# filter.net
KiCad netlist of a schematic drawn in Altium Designer
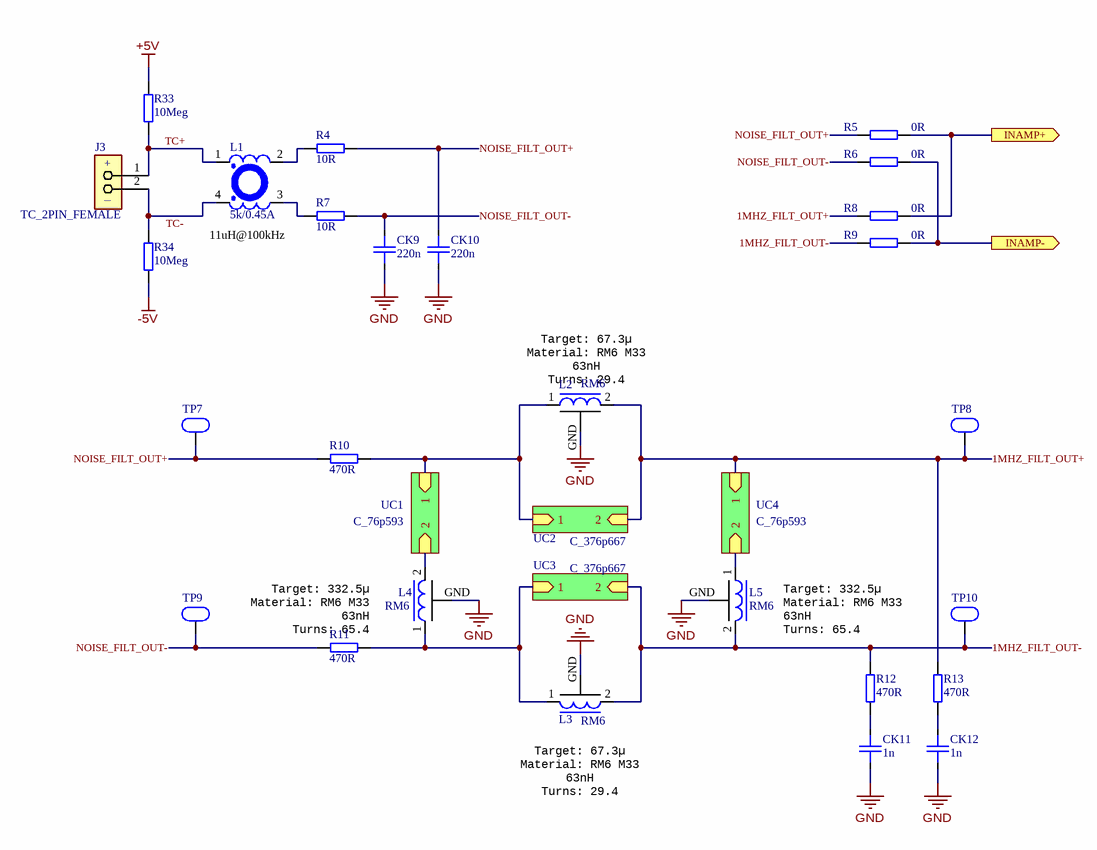
[diagram p0: filter.SchDoc]

(export (version "E")
  (design (tool "Eeschema 10.0.6"))
  (components
    (comp (ref "CK9")
      (value "220n")
      (footprint "CAPC1608X09N(SMC0603)")
      (description "C; 220n; 16V; 10%; X7R; ??;")
      (fields
        (field (name "MANUFACTURER") "TDK Corporation: C1608X7R1C224K080AC;;AVX Corporation: 0603YC224KAT2A;;Samsung: CL10B224KO8NNNC")
      )
      (libsource (lib "altium_sql") (part "CK"))
    )
    (comp (ref "CK10")
      (value "220n")
      (footprint "CAPC1608X09N(SMC0603)")
      (description "C; 220n; 16V; 10%; X7R; ??;")
      (fields
        (field (name "MANUFACTURER") "TDK Corporation: C1608X7R1C224K080AC;;AVX Corporation: 0603YC224KAT2A;;Samsung: CL10B224KO8NNNC")
      )
      (libsource (lib "altium_sql") (part "CK"))
    )
    (comp (ref "CK11")
      (value "1n")
      (footprint "CAPC2012X14N(SMC0805)")
      (description "C; 1n; 50V; 5%; NP0/C0G; ??;")
      (fields (field (name "MANUFACTURER") "YAGEO: CC0805JRNPO9BN102;;AVX: 0805 5A 102 JAT2A"))
      (libsource (lib "altium_sql") (part "CK"))
    )
    (comp (ref "CK12")
      (value "1n")
      (footprint "CAPC2012X14N(SMC0805)")
      (description "C; 1n; 50V; 5%; NP0/C0G; ??;")
      (fields (field (name "MANUFACTURER") "YAGEO: CC0805JRNPO9BN102;;AVX: 0805 5A 102 JAT2A"))
      (libsource (lib "altium_sql") (part "CK"))
    )
    (comp (ref "J3")
      (value "TC_2PIN_FEMALE")
      (footprint "TC_PCC-SMD")
      (description "Universal SMD thermocouple connector, 2 pin, Female")
      (libsource (lib "custom-footprints") (part "TC_2PIN_FEMALE"))
    )
    (comp (ref "L1")
      (value "5k/0.45A")
      (footprint "WE_744235110")
      (description "Flt; Common Mode Chokes; 0.8Ohm; 0.45A; 60V; 1x;")
      (fields (field (name "MANUFACTURER") "Würth: 744235110"))
      (libsource (lib "altium_sql") (part "L_COMP_43"))
    )
    (comp (ref "L2")
      (value "RM6")
      (footprint "RM6")
      (description "Inductor, RM6 Core")
      (libsource (lib "custom-footprints") (part "RM6"))
    )
    (comp (ref "L3")
      (value "RM6")
      (footprint "RM6")
      (description "Inductor, RM6 Core")
      (libsource (lib "") (part "RM6_1"))
    )
    (comp (ref "L4")
      (value "RM6")
      (footprint "RM6")
      (description "Inductor, RM6 Core")
      (libsource (lib "custom-footprints") (part "RM6"))
    )
    (comp (ref "L5")
      (value "RM6")
      (footprint "RM6")
      (description "Inductor, RM6 Core")
      (libsource (lib "custom-footprints") (part "RM6"))
    )
    (comp (ref "R4")
      (value "10R")
      (footprint "RESC2012X06N(SMR0805)")
      (description "R; 10R; 0.125W; 1%; 150V; Thick Film; ±200ppm/K; 1x;")
      (libsource (lib "altium_sql") (part "R"))
    )
    (comp (ref "R5")
      (value "0R")
      (footprint "RESC2012X06N(SMR0805)")
      (description "R; 0R; 0.125W; 1%; 150V; Thick Film; ±200ppm/K; 1x;")
      (fields
        (field (name "MANUFACTURER") "YAGEO: RC0805JR-100RL;;YAGEO: RC0805JR-130RL;;YAGEO: RC0805JR-070RL")
      )
      (libsource (lib "altium_sql") (part "R"))
    )
    (comp (ref "R6")
      (value "0R")
      (footprint "RESC2012X06N(SMR0805)")
      (description "R; 0R; 0.125W; 1%; 150V; Thick Film; ±200ppm/K; 1x;")
      (fields
        (field (name "MANUFACTURER") "YAGEO: RC0805JR-100RL;;YAGEO: RC0805JR-130RL;;YAGEO: RC0805JR-070RL")
      )
      (libsource (lib "altium_sql") (part "R"))
    )
    (comp (ref "R7")
      (value "10R")
      (footprint "RESC2012X06N(SMR0805)")
      (description "R; 10R; 0.125W; 1%; 150V; Thick Film; ±200ppm/K; 1x;")
      (libsource (lib "altium_sql") (part "R"))
    )
    (comp (ref "R8")
      (value "0R")
      (footprint "RESC2012X06N(SMR0805)")
      (description "R; 0R; 0.125W; 1%; 150V; Thick Film; ±200ppm/K; 1x;")
      (fields
        (field (name "MANUFACTURER") "YAGEO: RC0805JR-100RL;;YAGEO: RC0805JR-130RL;;YAGEO: RC0805JR-070RL")
      )
      (libsource (lib "altium_sql") (part "R"))
    )
    (comp (ref "R9")
      (value "0R")
      (footprint "RESC2012X06N(SMR0805)")
      (description "R; 0R; 0.125W; 1%; 150V; Thick Film; ±200ppm/K; 1x;")
      (fields
        (field (name "MANUFACTURER") "YAGEO: RC0805JR-100RL;;YAGEO: RC0805JR-130RL;;YAGEO: RC0805JR-070RL")
      )
      (libsource (lib "altium_sql") (part "R"))
    )
    (comp (ref "R10")
      (value "470R")
      (footprint "RESC1608X06N(SMR0603)")
      (description "R; 470R; 0.1W; 1%; 75V; Thick Film; ±100ppm/K; 1x;")
      (fields (field (name "MANUFACTURER") "Yageo: RC0603FR-07470RL;;Panasonic: ERJ3EKF4700V"))
      (libsource (lib "altium_sql") (part "R"))
    )
    (comp (ref "R11")
      (value "470R")
      (footprint "RESC1608X06N(SMR0603)")
      (description "R; 470R; 0.1W; 1%; 75V; Thick Film; ±100ppm/K; 1x;")
      (fields (field (name "MANUFACTURER") "Yageo: RC0603FR-07470RL;;Panasonic: ERJ3EKF4700V"))
      (libsource (lib "altium_sql") (part "R"))
    )
    (comp (ref "R12")
      (value "470R")
      (footprint "RESC1608X06N(SMR0603)")
      (description "R; 470R; 0.1W; 1%; 75V; Thick Film; ±100ppm/K; 1x;")
      (fields (field (name "MANUFACTURER") "Yageo: RC0603FR-07470RL;;Panasonic: ERJ3EKF4700V"))
      (libsource (lib "altium_sql") (part "R"))
    )
    (comp (ref "R13")
      (value "470R")
      (footprint "RESC1608X06N(SMR0603)")
      (description "R; 470R; 0.1W; 1%; 75V; Thick Film; ±100ppm/K; 1x;")
      (fields (field (name "MANUFACTURER") "Yageo: RC0603FR-07470RL;;Panasonic: ERJ3EKF4700V"))
      (libsource (lib "altium_sql") (part "R"))
    )
    (comp (ref "R33")
      (value "10Meg")
      (footprint "RESC2012X06N(SMR0805)")
      (description "R; 10Meg; 0.125W; 5%; 150V; Thick Film; ±100ppm/K; 1x;")
      (fields
        (field (name "MANUFACTURER") "YAGEO: RC0805JR-0710ML;;BC Components: MCU0805-50 1% P5 10M;;PANASONIC: ERJ 6GE Y J 106 V")
      )
      (libsource (lib "altium_sql") (part "R"))
    )
    (comp (ref "R34")
      (value "10Meg")
      (footprint "RESC2012X06N(SMR0805)")
      (description "R; 10Meg; 0.125W; 5%; 150V; Thick Film; ±100ppm/K; 1x;")
      (fields
        (field (name "MANUFACTURER") "YAGEO: RC0805JR-0710ML;;BC Components: MCU0805-50 1% P5 10M;;PANASONIC: ERJ 6GE Y J 106 V")
      )
      (libsource (lib "altium_sql") (part "R"))
    )
    (comp (ref "TP7")
      (value "Test Point")
      (footprint "SMD_Testpoint_Onelayer")
      (description "Con; Test Point; 1x; PCB; ??; ??V; ??A; ??; Tin; Contact;")
      (fields (field (name "MANUFACTURER") "Harwin: S1751-46R") (field (name "CONNECTOR_PART") "Contact"))
      (libsource (lib "altium_sql") (part "EJ+TESTPOINTXX0"))
    )
    (comp (ref "TP8")
      (value "Test Point")
      (footprint "SMD_Testpoint_Onelayer")
      (description "Con; Test Point; 1x; PCB; ??; ??V; ??A; ??; Tin; Contact;")
      (fields (field (name "MANUFACTURER") "Harwin: S1751-46R") (field (name "CONNECTOR_PART") "Contact"))
      (libsource (lib "altium_sql") (part "EJ+TESTPOINTXX0"))
    )
    (comp (ref "TP9")
      (value "Test Point")
      (footprint "SMD_Testpoint_Onelayer")
      (description "Con; Test Point; 1x; PCB; ??; ??V; ??A; ??; Tin; Contact;")
      (fields (field (name "MANUFACTURER") "Harwin: S1751-46R") (field (name "CONNECTOR_PART") "Contact"))
      (libsource (lib "altium_sql") (part "EJ+TESTPOINTXX0"))
    )
    (comp (ref "TP10")
      (value "Test Point")
      (footprint "SMD_Testpoint_Onelayer")
      (description "Con; Test Point; 1x; PCB; ??; ??V; ??A; ??; Tin; Contact;")
      (fields (field (name "MANUFACTURER") "Harwin: S1751-46R") (field (name "CONNECTOR_PART") "Contact"))
      (libsource (lib "altium_sql") (part "EJ+TESTPOINTXX0"))
    )
  )
  (nets
    (net (code "1") (name "+5V") (class "Default")
      (node (ref "R33") (pin "2") (pinfunction "2_2") (pintype "passive"))
    )
    (net (code "2") (name "-5V") (class "Default")
      (node (ref "R34") (pin "1") (pinfunction "1_1") (pintype "passive"))
    )
    (net (code "3") (name "/1") (class "Default")
      (node (ref "L2") (pin "1") (pinfunction "1_1") (pintype "passive"))
      (node (ref "R10") (pin "2") (pinfunction "2_2") (pintype "passive"))
    )
    (net (code "4") (name "/1MHZ_FILT_OUT+") (class "Default")
      (node (ref "L2") (pin "2") (pinfunction "2_2") (pintype "passive"))
      (node (ref "R13") (pin "2") (pinfunction "2_2") (pintype "passive"))
      (node (ref "R8") (pin "1") (pinfunction "1_1") (pintype "passive"))
      (node (ref "TP8") (pin "1") (pintype "passive"))
    )
    (net (code "5") (name "/1MHZ_FILT_OUT-") (class "Default")
      (node (ref "L3") (pin "2") (pinfunction "2_2") (pintype "passive"))
      (node (ref "L5") (pin "2") (pinfunction "2_2") (pintype "passive"))
      (node (ref "R12") (pin "2") (pinfunction "2_2") (pintype "passive"))
      (node (ref "R9") (pin "1") (pinfunction "1_1") (pintype "passive"))
      (node (ref "TP10") (pin "1") (pintype "passive"))
    )
    (net (code "6") (name "/1_1") (class "Default")
      (node (ref "L3") (pin "1") (pinfunction "1_1") (pintype "passive"))
      (node (ref "L4") (pin "1") (pinfunction "1_1") (pintype "passive"))
      (node (ref "R11") (pin "2") (pinfunction "2_2") (pintype "passive"))
    )
    (net (code "7") (name "/2") (class "Default")
      (node (ref "L5") (pin "1") (pinfunction "1_1") (pintype "passive"))
    )
    (net (code "8") (name "/2_1") (class "Default")
      (node (ref "L4") (pin "2") (pinfunction "2_2") (pintype "passive"))
    )
    (net (code "9") (name "/INAMP+") (class "Default")
      (node (ref "R5") (pin "2") (pinfunction "2_2") (pintype "passive"))
      (node (ref "R8") (pin "2") (pinfunction "2_2") (pintype "passive"))
    )
    (net (code "10") (name "/INAMP-") (class "Default")
      (node (ref "R6") (pin "2") (pinfunction "2_2") (pintype "passive"))
      (node (ref "R9") (pin "2") (pinfunction "2_2") (pintype "passive"))
    )
    (net (code "11") (name "/NOISE_FILT_OUT+") (class "Default")
      (node (ref "CK10") (pin "1") (pinfunction "1_1") (pintype "passive"))
      (node (ref "R10") (pin "1") (pinfunction "1_1") (pintype "passive"))
      (node (ref "R4") (pin "1") (pinfunction "1_1") (pintype "passive"))
      (node (ref "R5") (pin "1") (pinfunction "1_1") (pintype "passive"))
      (node (ref "TP7") (pin "1") (pintype "passive"))
    )
    (net (code "12") (name "/NOISE_FILT_OUT-") (class "Default")
      (node (ref "CK9") (pin "1") (pinfunction "1_1") (pintype "passive"))
      (node (ref "R11") (pin "1") (pinfunction "1_1") (pintype "passive"))
      (node (ref "R6") (pin "1") (pinfunction "1_1") (pintype "passive"))
      (node (ref "R7") (pin "2") (pinfunction "2_2") (pintype "passive"))
      (node (ref "TP9") (pin "1") (pintype "passive"))
    )
    (net (code "13") (name "/TC+") (class "Default")
      (node (ref "J3") (pin "1") (pinfunction "1_1") (pintype "passive"))
      (node (ref "L1") (pin "1") (pinfunction "L1A_1") (pintype "passive"))
      (node (ref "R33") (pin "1") (pinfunction "1_1") (pintype "passive"))
    )
    (net (code "14") (name "/TC-") (class "Default")
      (node (ref "J3") (pin "2") (pinfunction "2_2") (pintype "passive"))
      (node (ref "L1") (pin "4") (pinfunction "L2B_4") (pintype "passive"))
      (node (ref "R34") (pin "2") (pinfunction "2_2") (pintype "passive"))
    )
    (net (code "15") (name "GND") (class "Default")
      (node (ref "CK10") (pin "2") (pinfunction "2_2") (pintype "passive"))
      (node (ref "CK11") (pin "1") (pinfunction "1_1") (pintype "passive"))
      (node (ref "CK12") (pin "1") (pinfunction "1_1") (pintype "passive"))
      (node (ref "CK9") (pin "2") (pinfunction "2_2") (pintype "passive"))
      (node (ref "L2") (pin "GND") (pinfunction "GND_GND") (pintype "power_in"))
      (node (ref "L3") (pin "GND") (pinfunction "GND_GND") (pintype "power_in"))
      (node (ref "L4") (pin "GND") (pinfunction "GND_GND") (pintype "power_in"))
      (node (ref "L5") (pin "GND") (pinfunction "GND_GND") (pintype "power_in"))
    )
    (net (code "16") (name "Net-(CK11-Pad2)") (class "Default")
      (node (ref "CK11") (pin "2") (pinfunction "2_2") (pintype "passive"))
      (node (ref "R12") (pin "1") (pinfunction "1_1") (pintype "passive"))
    )
    (net (code "17") (name "Net-(CK12-Pad2)") (class "Default")
      (node (ref "CK12") (pin "2") (pinfunction "2_2") (pintype "passive"))
      (node (ref "R13") (pin "1") (pinfunction "1_1") (pintype "passive"))
    )
    (net (code "18") (name "Net-(L1-L1B)") (class "Default")
      (node (ref "L1") (pin "2") (pinfunction "L1B_2") (pintype "passive"))
      (node (ref "R4") (pin "2") (pinfunction "2_2") (pintype "passive"))
    )
    (net (code "19") (name "Net-(L1-L2A)") (class "Default")
      (node (ref "L1") (pin "3") (pinfunction "L2A_3") (pintype "passive"))
      (node (ref "R7") (pin "1") (pinfunction "1_1") (pintype "passive"))
    )
  )
)
